# 10_Misc.net
KiCad netlist of a schematic drawn in Altium Designer
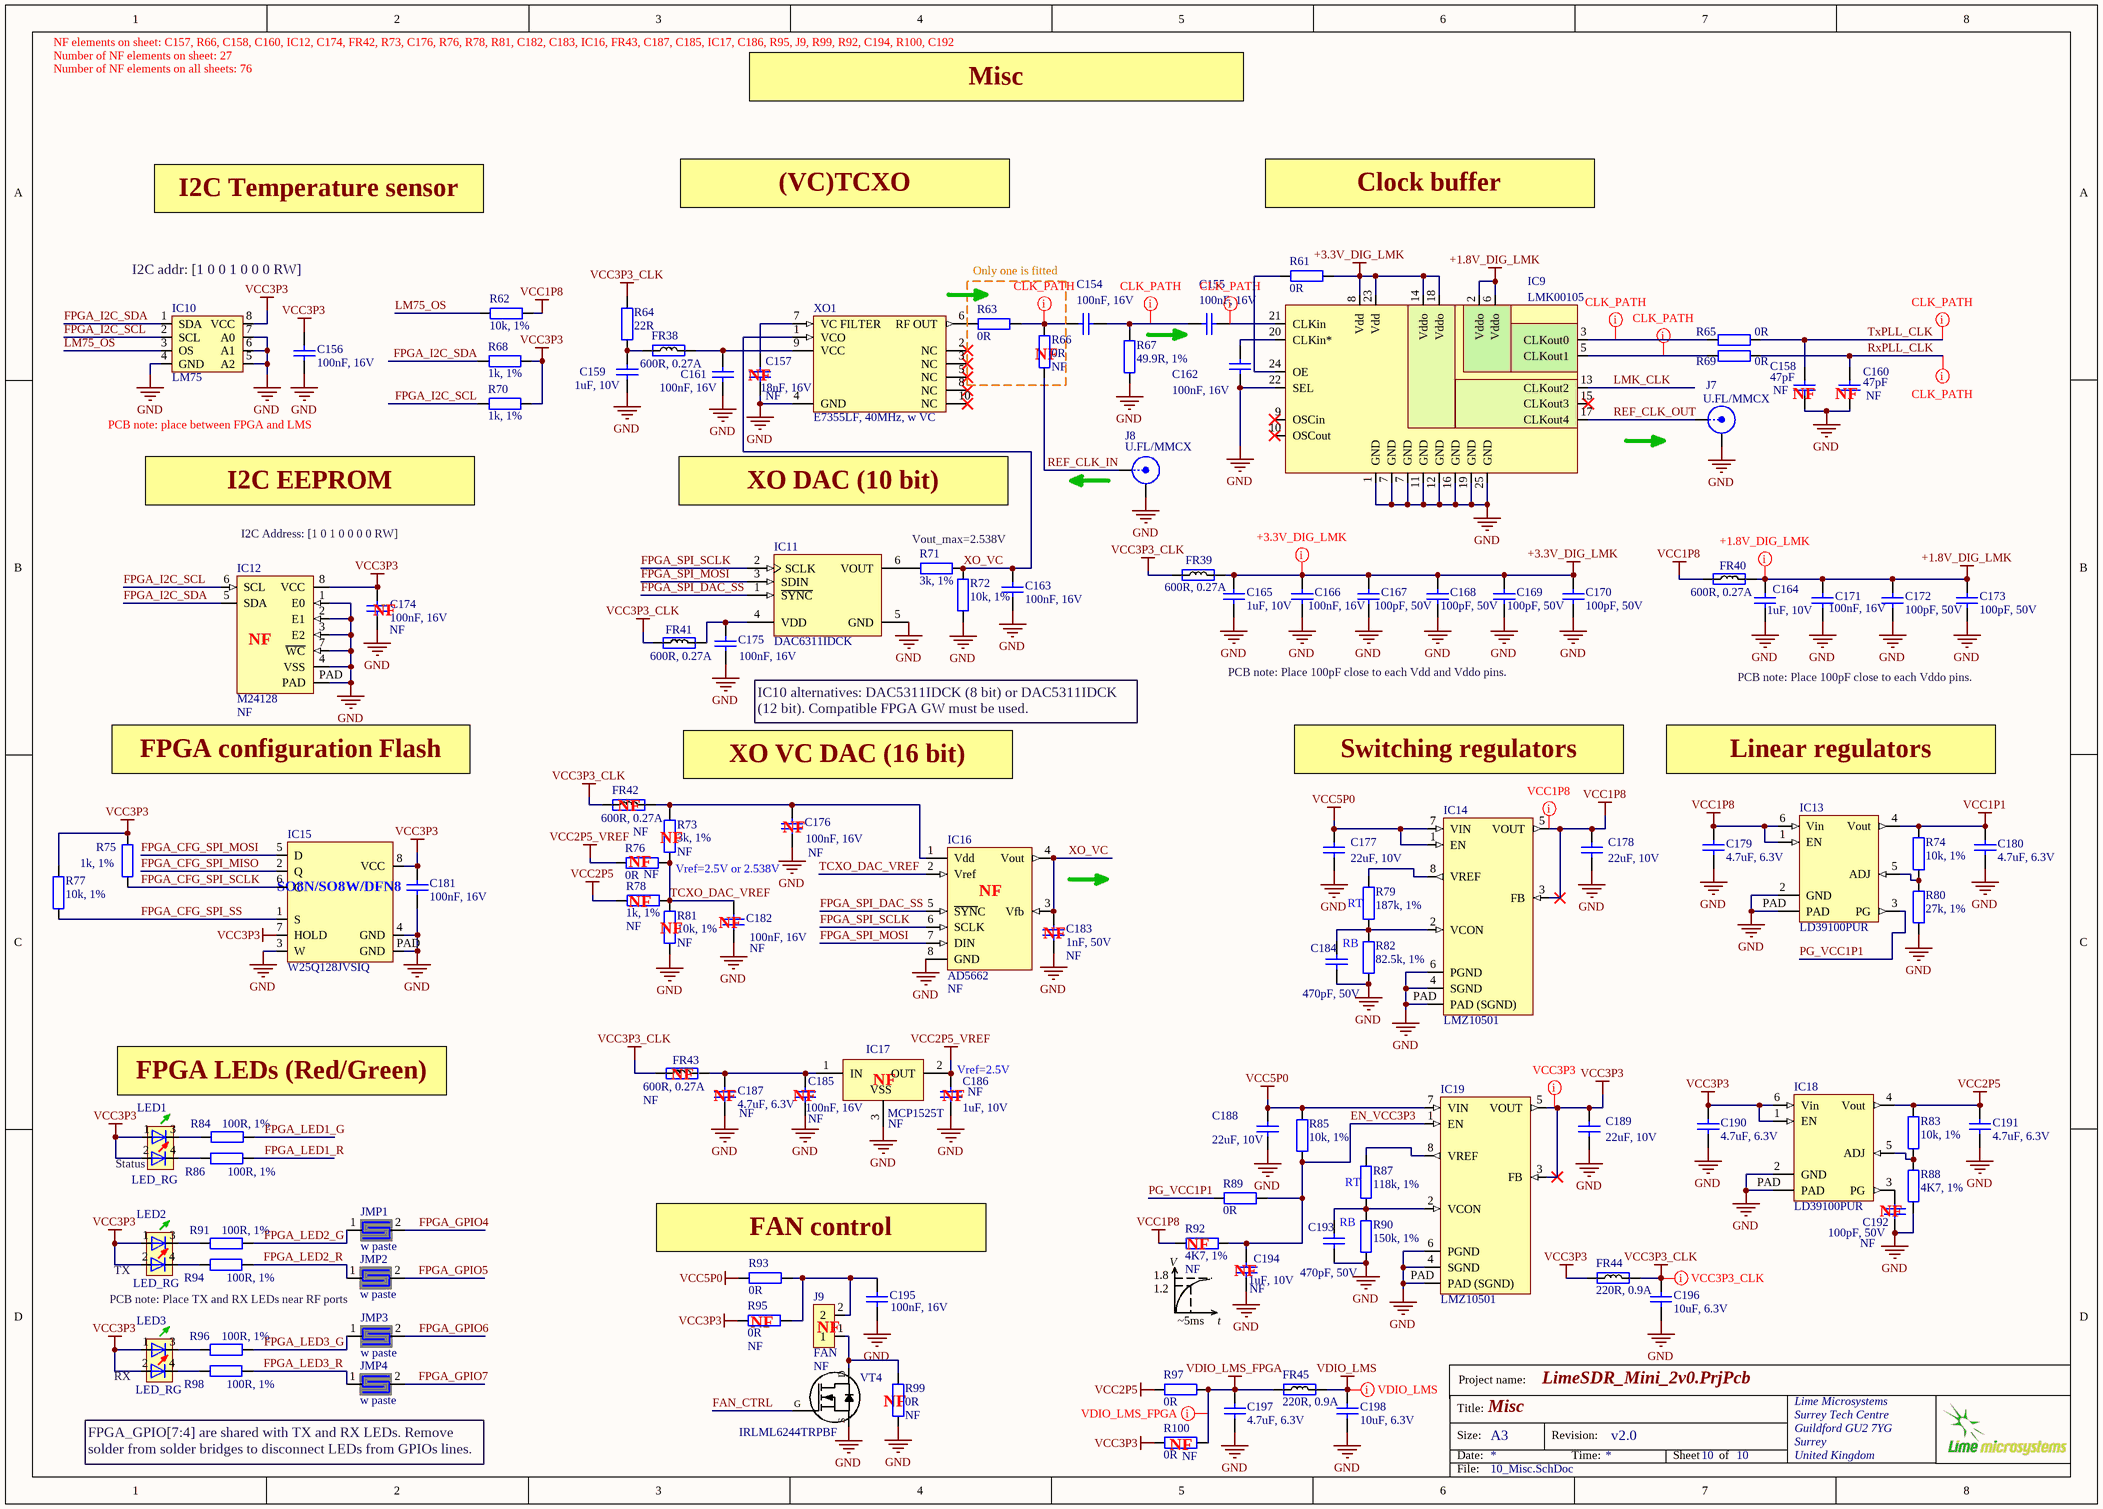
[diagram p0: 10_Misc.SchDoc]

(export (version "E")
  (design (tool "Eeschema 10.0.6"))
  (components
    (comp (ref "C154")
      (value "100nF, 16V")
      (footprint "CAP0402")
      (fields
        (field (name "MANUFACTURER") "Murata Electronics")
        (field (name "TOLERANCE") "10 %")
        (field (name "MANUFACTURER PART NUMBER") "GRM155R71C104KA88D")
      )
      (libsource (lib "LimeMicroAltiumLib_schLib") (part "Cap_0402"))
    )
    (comp (ref "C155")
      (value "100nF, 16V")
      (footprint "CAP0402")
      (fields
        (field (name "MANUFACTURER") "Murata Electronics")
        (field (name "TOLERANCE") "10 %")
        (field (name "MANUFACTURER PART NUMBER") "GRM155R71C104KA88D")
      )
      (libsource (lib "LimeMicroAltiumLib_schLib") (part "Cap_0402"))
    )
    (comp (ref "C156")
      (value "100nF, 16V")
      (footprint "CAP0402")
      (fields
        (field (name "TOLERANCE") "10 %")
        (field (name "MANUFACTURER") "Murata Electronics")
        (field (name "MANUFACTURER PART NUMBER") "GRM155R71C104KA88D")
      )
      (libsource (lib "") (part "Cap_0603_1"))
    )
    (comp (ref "C157")
      (value "18nF, 16V")
      (footprint "CAP0402")
      (fields
        (field (name "ASSEMBLY INFO") "NF")
        (field (name "MANUFACTURER") "Yageo")
        (field (name "TOLERANCE") "±10%")
      )
      (libsource (lib "LimeMicroAltiumLib_schLib") (part "Cap_0402"))
    )
    (comp (ref "C158")
      (value "47pF")
      (footprint "CAP0402")
      (fields
        (field (name "TOLERANCE") "±1%")
        (field (name "MANUFACTURER") "TDK Corporation")
        (field (name "ASSEMBLY INFO") "NF")
      )
      (libsource (lib "LimeMicroAltiumLib_schLib") (part "Cap_0402"))
    )
    (comp (ref "C159")
      (value "1uF, 10V")
      (footprint "CAP0402")
      (fields (field (name "MANUFACTURER") "TDK"))
      (libsource (lib "LimeMicroAltiumLib_schLib") (part "Cap_0402"))
    )
    (comp (ref "C160")
      (value "47pF")
      (footprint "CAP0402")
      (fields
        (field (name "TOLERANCE") "±1%")
        (field (name "MANUFACTURER") "TDK Corporation")
        (field (name "ASSEMBLY INFO") "NF")
      )
      (libsource (lib "LimeMicroAltiumLib_schLib") (part "Cap_0402"))
    )
    (comp (ref "C161")
      (value "100nF, 16V")
      (footprint "CAP0402")
      (fields
        (field (name "MANUFACTURER") "Murata Electronics")
        (field (name "TOLERANCE") "10 %")
        (field (name "MANUFACTURER PART NUMBER") "GRM155R71C104KA88D")
      )
      (libsource (lib "LimeMicroAltiumLib_schLib") (part "Cap_0402"))
    )
    (comp (ref "C162")
      (value "100nF, 16V")
      (footprint "CAP0402")
      (fields
        (field (name "MANUFACTURER") "Murata Electronics")
        (field (name "TOLERANCE") "10 %")
        (field (name "MANUFACTURER PART NUMBER") "GRM155R71C104KA88D")
      )
      (libsource (lib "LimeMicroAltiumLib_schLib") (part "Cap_0402"))
    )
    (comp (ref "C163")
      (value "100nF, 16V")
      (footprint "CAP0402")
      (fields
        (field (name "MANUFACTURER") "Murata Electronics")
        (field (name "TOLERANCE") "10 %")
        (field (name "MANUFACTURER PART NUMBER") "GRM155R71C104KA88D")
      )
      (libsource (lib "LimeMicroAltiumLib_schLib") (part "Cap_0402"))
    )
    (comp (ref "C164")
      (value "1uF, 10V")
      (footprint "CAP0402")
      (fields (field (name "MANUFACTURER") "TDK"))
      (libsource (lib "LimeMicroAltiumLib_schLib") (part "Cap_0402"))
    )
    (comp (ref "C165")
      (value "1uF, 10V")
      (footprint "CAP0402")
      (fields (field (name "MANUFACTURER") "TDK"))
      (libsource (lib "LimeMicroAltiumLib_schLib") (part "Cap_0402"))
    )
    (comp (ref "C166")
      (value "100nF, 16V")
      (footprint "CAP0402")
      (fields
        (field (name "MANUFACTURER") "Murata Electronics")
        (field (name "TOLERANCE") "10 %")
        (field (name "MANUFACTURER PART NUMBER") "GRM155R71C104KA88D")
      )
      (libsource (lib "LimeMicroAltiumLib_schLib") (part "Cap_0402"))
    )
    (comp (ref "C167")
      (value "100pF, 50V")
      (footprint "CAP0402")
      (fields (field (name "MANUFACTURER") "Yageo") (field (name "TOLERANCE") "±5%"))
      (libsource (lib "LimeMicroAltiumLib_schLib") (part "Cap_0402"))
    )
    (comp (ref "C168")
      (value "100pF, 50V")
      (footprint "CAP0402")
      (fields (field (name "MANUFACTURER") "Yageo") (field (name "TOLERANCE") "±5%"))
      (libsource (lib "LimeMicroAltiumLib_schLib") (part "Cap_0402"))
    )
    (comp (ref "C169")
      (value "100pF, 50V")
      (footprint "CAP0402")
      (fields (field (name "MANUFACTURER") "Yageo") (field (name "TOLERANCE") "±5%"))
      (libsource (lib "LimeMicroAltiumLib_schLib") (part "Cap_0402"))
    )
    (comp (ref "C170")
      (value "100pF, 50V")
      (footprint "CAP0402")
      (fields (field (name "MANUFACTURER") "Yageo") (field (name "TOLERANCE") "±5%"))
      (libsource (lib "LimeMicroAltiumLib_schLib") (part "Cap_0402"))
    )
    (comp (ref "C171")
      (value "100nF, 16V")
      (footprint "CAP0402")
      (fields
        (field (name "MANUFACTURER") "Murata Electronics")
        (field (name "TOLERANCE") "10 %")
        (field (name "MANUFACTURER PART NUMBER") "GRM155R71C104KA88D")
      )
      (libsource (lib "LimeMicroAltiumLib_schLib") (part "Cap_0402"))
    )
    (comp (ref "C172")
      (value "100pF, 50V")
      (footprint "CAP0402")
      (fields (field (name "MANUFACTURER") "Yageo") (field (name "TOLERANCE") "±5%"))
      (libsource (lib "LimeMicroAltiumLib_schLib") (part "Cap_0402"))
    )
    (comp (ref "C173")
      (value "100pF, 50V")
      (footprint "CAP0402")
      (fields (field (name "MANUFACTURER") "Yageo") (field (name "TOLERANCE") "±5%"))
      (libsource (lib "LimeMicroAltiumLib_schLib") (part "Cap_0402"))
    )
    (comp (ref "C174")
      (value "100nF, 16V")
      (footprint "CAP0402")
      (fields
        (field (name "TOLERANCE") "10 %")
        (field (name "MANUFACTURER") "Murata Electronics")
        (field (name "MANUFACTURER PART NUMBER") "GRM155R71C104KA88D")
        (field (name "ASSEMBLY INFO") "NF")
      )
      (libsource (lib "") (part "Cap_0603_1"))
    )
    (comp (ref "C175")
      (value "100nF, 16V")
      (footprint "CAP0402")
      (fields
        (field (name "TOLERANCE") "10 %")
        (field (name "MANUFACTURER") "Murata Electronics")
        (field (name "MANUFACTURER PART NUMBER") "GRM155R71C104KA88D")
      )
      (libsource (lib "") (part "Cap_0603_1"))
    )
    (comp (ref "C176")
      (value "100nF, 16V")
      (footprint "CAP0402")
      (fields
        (field (name "TOLERANCE") "10 %")
        (field (name "MANUFACTURER") "Murata Electronics")
        (field (name "MANUFACTURER PART NUMBER") "GRM155R71C104KA88D")
        (field (name "ASSEMBLY INFO") "NF")
      )
      (libsource (lib "") (part "Cap_0603_1"))
    )
    (comp (ref "C177")
      (value "22uF, 10V")
      (footprint "CAP0603")
      (fields (field (name "TOLERANCE") "20 %") (field (name "MANUFACTURER") "TDK Corporation"))
      (libsource (lib "") (part "Cap_0603_1"))
    )
    (comp (ref "C178")
      (value "22uF, 10V")
      (footprint "CAP0603")
      (fields (field (name "TOLERANCE") "20 %") (field (name "MANUFACTURER") "TDK Corporation"))
      (libsource (lib "") (part "Cap_0603_1"))
    )
    (comp (ref "C179")
      (value "4.7uF, 6.3V")
      (footprint "CAP0402")
      (fields
        (field (name "MANUFACTURER") "Murata Electronics North America")
        (field (name "TOLERANCE") "±20%")
      )
      (libsource (lib "LimeMicroAltiumLib_schLib") (part "Cap_0402"))
    )
    (comp (ref "C180")
      (value "4.7uF, 6.3V")
      (footprint "CAP0402")
      (fields
        (field (name "MANUFACTURER") "Murata Electronics North America")
        (field (name "TOLERANCE") "±20%")
      )
      (libsource (lib "LimeMicroAltiumLib_schLib") (part "Cap_0402"))
    )
    (comp (ref "C181")
      (value "100nF, 16V")
      (footprint "CAP0402")
      (fields
        (field (name "TOLERANCE") "10 %")
        (field (name "MANUFACTURER") "Murata Electronics")
        (field (name "MANUFACTURER PART NUMBER") "GRM155R71C104KA88D")
      )
      (libsource (lib "") (part "Cap_0603_1"))
    )
    (comp (ref "C182")
      (value "100nF, 16V")
      (footprint "LimeMicroAltiumLib_pcbLib_r03:CAP0402")
      (fields
        (field (name "TOLERANCE") "10 %")
        (field (name "MANUFACTURER") "Murata Electronics")
        (field (name "ASSEMBLY INFO") "NF")
      )
      (libsource (lib "LimeFPGAboard_schLib") (part "Cap_0603"))
    )
    (comp (ref "C183")
      (value "1nF, 50V")
      (footprint "LimeMicroAltiumLib_pcbLib_r03:CAP0402")
      (fields
        (field (name "ASSEMBLY INFO") "NF")
        (field (name "TOLERANCE") "10 %")
        (field (name "MANUFACTURER") "Murata Electronics")
      )
      (libsource (lib "") (part "Cap_0402_1"))
    )
    (comp (ref "C184")
      (value "470pF, 50V")
      (footprint "CAP0402")
      (fields (field (name "TOLERANCE") "±5%") (field (name "MANUFACTURER") "TDK Corporation"))
      (libsource (lib "LimeMicroAltiumLib_schLib") (part "Cap_0402"))
    )
    (comp (ref "C185")
      (value "100nF, 16V")
      (footprint "LimeMicroAltiumLib_pcbLib_r03:CAP0402")
      (fields
        (field (name "TOLERANCE") "10 %")
        (field (name "MANUFACTURER") "Murata Electronics")
        (field (name "ASSEMBLY INFO") "NF")
      )
      (libsource (lib "LimeFPGAboard_schLib") (part "Cap_0603"))
    )
    (comp (ref "C186")
      (value "1uF, 10V")
      (footprint "CAP0402")
      (fields (field (name "ASSEMBLY INFO") "NF") (field (name "MANUFACTURER") "TDK"))
      (libsource (lib "LimeMicroAltiumLib_schLib") (part "Cap_0402"))
    )
    (comp (ref "C187")
      (value "4.7uF, 6.3V")
      (footprint "CAP0402")
      (fields
        (field (name "ASSEMBLY INFO") "NF")
        (field (name "MANUFACTURER") "Murata Electronics North America")
        (field (name "TOLERANCE") "±20%")
      )
      (libsource (lib "LimeMicroAltiumLib_schLib") (part "Cap_0402"))
    )
    (comp (ref "C188")
      (value "22uF, 10V")
      (footprint "CAP0603")
      (fields (field (name "TOLERANCE") "20 %") (field (name "MANUFACTURER") "TDK Corporation"))
      (libsource (lib "") (part "Cap_0603_1"))
    )
    (comp (ref "C189")
      (value "22uF, 10V")
      (footprint "CAP0603")
      (fields (field (name "TOLERANCE") "20 %") (field (name "MANUFACTURER") "TDK Corporation"))
      (libsource (lib "") (part "Cap_0603_1"))
    )
    (comp (ref "C190")
      (value "4.7uF, 6.3V")
      (footprint "CAP0402")
      (fields
        (field (name "MANUFACTURER") "Murata Electronics North America")
        (field (name "TOLERANCE") "±20%")
      )
      (libsource (lib "LimeMicroAltiumLib_schLib") (part "Cap_0402"))
    )
    (comp (ref "C191")
      (value "4.7uF, 6.3V")
      (footprint "CAP0402")
      (fields
        (field (name "MANUFACTURER") "Murata Electronics North America")
        (field (name "TOLERANCE") "±20%")
      )
      (libsource (lib "LimeMicroAltiumLib_schLib") (part "Cap_0402"))
    )
    (comp (ref "C192")
      (value "100pF, 50V")
      (footprint "CAP0402")
      (fields
        (field (name "ASSEMBLY INFO") "NF")
        (field (name "MANUFACTURER") "Yageo")
        (field (name "TOLERANCE") "±5%")
      )
      (libsource (lib "LimeMicroAltiumLib_schLib") (part "Cap_0402"))
    )
    (comp (ref "C193")
      (value "470pF, 50V")
      (footprint "CAP0402")
      (fields (field (name "TOLERANCE") "±5%") (field (name "MANUFACTURER") "TDK Corporation"))
      (libsource (lib "LimeMicroAltiumLib_schLib") (part "Cap_0402"))
    )
    (comp (ref "C194")
      (value "1uF, 10V")
      (footprint "CAP0402")
      (fields (field (name "ASSEMBLY INFO") "NF") (field (name "MANUFACTURER") "TDK"))
      (libsource (lib "LimeMicroAltiumLib_schLib") (part "Cap_0402"))
    )
    (comp (ref "C195")
      (value "100nF, 16V")
      (footprint "CAP0402")
      (fields
        (field (name "TOLERANCE") "10 %")
        (field (name "MANUFACTURER") "Murata Electronics")
        (field (name "MANUFACTURER PART NUMBER") "GRM155R71C104KA88D")
      )
      (libsource (lib "") (part "Cap_0603_1"))
    )
    (comp (ref "C196")
      (value "10uF, 6.3V")
      (footprint "CAP0603")
      (fields (field (name "TOLERANCE") "±20%") (field (name "MANUFACTURER") "Yageo"))
      (libsource (lib "") (part "Cap_0603_1"))
    )
    (comp (ref "C197")
      (value "4.7uF, 6.3V")
      (footprint "CAP0402")
      (fields
        (field (name "MANUFACTURER") "Murata Electronics North America")
        (field (name "TOLERANCE") "±20%")
      )
      (libsource (lib "LimeMicroAltiumLib_schLib") (part "Cap_0402"))
    )
    (comp (ref "C198")
      (value "10uF, 6.3V")
      (footprint "CAP0603")
      (fields (field (name "TOLERANCE") "±20%") (field (name "MANUFACTURER") "Yageo"))
      (libsource (lib "") (part "Cap_0603_1"))
    )
    (comp (ref "FR38")
      (value "600R, 0.27A")
      (footprint "RES0201")
      (fields (field (name "MANUFACTURER") "Taiyo Yuden"))
      (libsource (lib "LimeMicroAltiumLib_schLib") (part "Ferrite"))
    )
    (comp (ref "FR39")
      (value "600R, 0.27A")
      (footprint "RES0201")
      (fields (field (name "MANUFACTURER") "Taiyo Yuden"))
      (libsource (lib "LimeMicroAltiumLib_schLib") (part "Ferrite"))
    )
    (comp (ref "FR40")
      (value "600R, 0.27A")
      (footprint "RES0201")
      (fields (field (name "MANUFACTURER") "Taiyo Yuden"))
      (libsource (lib "LimeMicroAltiumLib_schLib") (part "Ferrite"))
    )
    (comp (ref "FR41")
      (value "600R, 0.27A")
      (footprint "RES0201")
      (fields (field (name "MANUFACTURER") "Taiyo Yuden"))
      (libsource (lib "LimeMicroAltiumLib_schLib") (part "Ferrite"))
    )
    (comp (ref "FR42")
      (value "600R, 0.27A")
      (footprint "RES0201")
      (fields (field (name "MANUFACTURER") "Taiyo Yuden") (field (name "ASSEMBLY INFO") "NF"))
      (libsource (lib "LimeMicroAltiumLib_schLib") (part "Ferrite"))
    )
    (comp (ref "FR43")
      (value "600R, 0.27A")
      (footprint "RES0201")
      (fields (field (name "MANUFACTURER") "Taiyo Yuden") (field (name "ASSEMBLY INFO") "NF"))
      (libsource (lib "LimeMicroAltiumLib_schLib") (part "Ferrite"))
    )
    (comp (ref "FR44")
      (value "220R, 0.9A")
      (footprint "RES0402")
      (fields (field (name "MANUFACTURER") "TDK Corporation"))
      (libsource (lib "LimeFPGAboard_schLib") (part "Ferrite"))
    )
    (comp (ref "FR45")
      (value "220R, 0.9A")
      (footprint "RES0402")
      (fields (field (name "MANUFACTURER") "TDK Corporation"))
      (libsource (lib "LimeFPGAboard_schLib") (part "Ferrite"))
    )
    (comp (ref "IC9")
      (value "LMK00105")
      (footprint "LMK00105SQ")
      (fields (field (name "MANUFACTURER") "Texas Instruments"))
      (libsource (lib "LimeMicroAltiumLib_schLib") (part "LMK00105"))
    )
    (comp (ref "IC10")
      (value "LM75")
      (footprint "HWSON8_LM75")
      (fields (field (name "MANUFACTURER") "NXP Semiconductors"))
      (libsource (lib "LimeMicroAltiumLib_schLib") (part "LM75"))
    )
    (comp (ref "IC11")
      (value "DAC6311IDCK")
      (footprint "AD5601_SOT23-6")
      (fields (field (name "MANUFACTURER") "Texas Instruments"))
      (libsource (lib "LimeMicroAltiumLib_schLib") (part "AD5601BKSZ-REEL7"))
    )
    (comp (ref "IC12")
      (value "M24128")
      (footprint "M24128-DFMC6TG")
      (fields (field (name "MANUFACTURER") "STMicroelectronics") (field (name "ASSEMBLY INFO") "NF"))
      (libsource (lib "LimeMicroAltiumLib_schLib") (part "M24128-DFMC6TG"))
    )
    (comp (ref "IC13")
      (value "LD39100PUR")
      (footprint "LD39100PUR")
      (fields (field (name "MANUFACTURER") "STMicroelectronics"))
      (libsource (lib "LimeMicroAltiumLib_schLib") (part "LD39100PUR"))
    )
    (comp (ref "IC14")
      (value "LMZ10501")
      (footprint "LMZ10501")
      (fields (field (name "MANUFACTURER") "Texas Instruments"))
      (libsource (lib "LimeMicroAltiumLib_schLib") (part "LMZ10501"))
    )
    (comp (ref "IC15")
      (value "W25Q128JVSIQ")
      (footprint "S25FL164K_WSON8_DFN6")
      (fields (field (name "MANUFACTURER") "Winbond"))
      (libsource (lib "LimeMicroAltiumLib_schLib_r03") (part "M25P40_with_pad"))
    )
    (comp (ref "IC16")
      (value "AD5662")
      (footprint "LimeMicroAltiumLib_pcbLib_r03:AD5662_SOT23-8")
      (fields (field (name "MANUFACTURER") "Analog Devices Inc.") (field (name "ASSEMBLY INFO") "NF"))
      (libsource (lib "LimeMicroAltiumLib_schLib") (part "AD5662"))
    )
    (comp (ref "IC17")
      (value "MCP1525T")
      (footprint "LimeMicroAltiumLib_pcbLib_r03:SOT23-3_v2")
      (description "2.5V Voltage Reference, 3-Pin SOT-23, Industrial Temperature, Tape and Reel")
      (fields
        (field (name "MANUFACTURER") "Microchip Technology")
        (field (name "TOLERANCE") "±1%")
        (field (name "ASSEMBLY INFO") "NF")
      )
      (libsource (lib "LimeMicroAltiumLib_schLib") (part "MCP1525T-I/TT"))
    )
    (comp (ref "IC18")
      (value "LD39100PUR")
      (footprint "LD39100PUR")
      (fields (field (name "MANUFACTURER") "STMicroelectronics"))
      (libsource (lib "LimeMicroAltiumLib_schLib") (part "LD39100PUR"))
    )
    (comp (ref "IC19")
      (value "LMZ10501")
      (footprint "LMZ10501")
      (fields (field (name "MANUFACTURER") "Texas Instruments"))
      (libsource (lib "LimeMicroAltiumLib_schLib") (part "LMZ10501"))
    )
    (comp (ref "J7")
      (value "U.FL/MMCX")
      (footprint "MMCX_UFL_conn_u")
      (description "CONN UMC RCPT STR 50 OHM SMD")
      (fields (field (name "MANUFACTURER") "Molex, LLC"))
      (libsource (lib "LimeMicroAltiumLib_schLib") (part "RF_IF_connector"))
    )
    (comp (ref "J8")
      (value "U.FL/MMCX")
      (footprint "MMCX_UFL_conn_u")
      (description "CONN UMC RCPT STR 50 OHM SMD")
      (fields (field (name "MANUFACTURER") "Molex, LLC"))
      (libsource (lib "LimeMicroAltiumLib_schLib") (part "RF_IF_connector"))
    )
    (comp (ref "J9")
      (value "FAN")
      (footprint "Header2x1_TH_v2")
      (fields (field (name "ASSEMBLY INFO") "NF") (field (name "MANUFACTURER") "3M"))
      (libsource (lib "LimeFPGAboard_schLib") (part "Jumper"))
    )
    (comp (ref "JMP1")
      (value "w paste")
      (footprint "JUMPER_0P15_W_PASTE")
      (libsource (lib "LimeMicroAltiumLib_schLib_r03") (part "JUMPER_W_PASTE"))
    )
    (comp (ref "JMP2")
      (value "w paste")
      (footprint "JUMPER_0P15_W_PASTE")
      (libsource (lib "LimeMicroAltiumLib_schLib_r03") (part "JUMPER_W_PASTE"))
    )
    (comp (ref "JMP3")
      (value "w paste")
      (footprint "JUMPER_0P15_W_PASTE")
      (libsource (lib "LimeMicroAltiumLib_schLib_r03") (part "JUMPER_W_PASTE"))
    )
    (comp (ref "JMP4")
      (value "w paste")
      (footprint "JUMPER_0P15_W_PASTE")
      (libsource (lib "LimeMicroAltiumLib_schLib_r03") (part "JUMPER_W_PASTE"))
    )
    (comp (ref "LED1")
      (value "LED_RG")
      (footprint "LED-2x0603")
      (fields (field (name "MANUFACTURER") "Avago Technologies US Inc."))
      (libsource (lib "LimeMicroAltiumLib_schLib") (part "LED_green_red_SMD"))
    )
    (comp (ref "LED2")
      (value "LED_RG")
      (footprint "LED-2x0603")
      (fields (field (name "MANUFACTURER") "Avago Technologies US Inc."))
      (libsource (lib "LimeMicroAltiumLib_schLib") (part "LED_green_red_SMD"))
    )
    (comp (ref "LED3")
      (value "LED_RG")
      (footprint "LED-2x0603")
      (fields (field (name "MANUFACTURER") "Avago Technologies US Inc."))
      (libsource (lib "LimeMicroAltiumLib_schLib") (part "LED_green_red_SMD"))
    )
    (comp (ref "R61")
      (value "0R")
      (footprint "RES0402")
      (fields (field (name "MANUFACTURER") "Yageo") (field (name "TOLERANCE") "Jumper"))
      (libsource (lib "LimeMicroAltiumLib_schLib") (part "Res_0402"))
    )
    (comp (ref "R62")
      (value "10k, 1%")
      (footprint "RES0402")
      (fields (field (name "MANUFACTURER") "Yageo") (field (name "TOLERANCE") "±1%"))
      (libsource (lib "LimeMicroAltiumLib_schLib") (part "Res_0402"))
    )
    (comp (ref "R63")
      (value "0R")
      (footprint "RES0402")
      (fields (field (name "MANUFACTURER") "Yageo") (field (name "TOLERANCE") "Jumper"))
      (libsource (lib "LimeMicroAltiumLib_schLib") (part "Res_0402"))
    )
    (comp (ref "R64")
      (value "22R")
      (footprint "RES0402")
      (fields (field (name "TOLERANCE") "±1%") (field (name "MANUFACTURER") "Yageo"))
      (libsource (lib "LimeFPGAboard_schLib") (part "Res_0402"))
    )
    (comp (ref "R65")
      (value "0R")
      (footprint "RES0402")
      (fields (field (name "MANUFACTURER") "Yageo") (field (name "TOLERANCE") "Jumper"))
      (libsource (lib "LimeFPGAboard_schLib") (part "Res_0402"))
    )
    (comp (ref "R66")
      (value "0R")
      (footprint "RES0402")
      (fields
        (field (name "ASSEMBLY INFO") "NF")
        (field (name "MANUFACTURER") "Yageo")
        (field (name "TOLERANCE") "Jumper")
      )
      (libsource (lib "LimeMicroAltiumLib_schLib") (part "Res_0402"))
    )
    (comp (ref "R67")
      (value "49.9R, 1%")
      (footprint "RES0402")
      (fields
        (field (name "TOLERANCE") "±1%")
        (field (name "MANUFACTURER") "Samsung Electro-Mechanics America, Inc.")
      )
      (libsource (lib "LimeMicroAltiumLib_schLib") (part "Res_0402"))
    )
    (comp (ref "R68")
      (value "1k, 1%")
      (footprint "RES0402")
      (fields (field (name "MANUFACTURER") "Stackpole Electronics Inc") (field (name "TOLERANCE") "±1%"))
      (libsource (lib "LimeMicroAltiumLib_schLib") (part "Res_0402"))
    )
    (comp (ref "R69")
      (value "0R")
      (footprint "RES0402")
      (fields (field (name "MANUFACTURER") "Yageo") (field (name "TOLERANCE") "Jumper"))
      (libsource (lib "LimeFPGAboard_schLib") (part "Res_0402"))
    )
    (comp (ref "R70")
      (value "1k, 1%")
      (footprint "RES0402")
      (fields (field (name "MANUFACTURER") "Stackpole Electronics Inc") (field (name "TOLERANCE") "±1%"))
      (libsource (lib "LimeMicroAltiumLib_schLib") (part "Res_0402"))
    )
    (comp (ref "R71")
      (value "3k, 1%")
      (footprint "RES0402")
      (fields (field (name "TOLERANCE") "±1%") (field (name "MANUFACTURER") "Vishay Dale"))
      (libsource (lib "LimeMicroAltiumLib_schLib") (part "Res_0402"))
    )
    (comp (ref "R72")
      (value "10k, 1%")
      (footprint "RES0402")
      (fields (field (name "MANUFACTURER") "Yageo") (field (name "TOLERANCE") "±1%"))
      (libsource (lib "LimeMicroAltiumLib_schLib") (part "Res_0402"))
    )
    (comp (ref "R73")
      (value "3k, 1%")
      (footprint "LimeMicroAltiumLib_pcbLib_r03:RES0402")
      (fields
        (field (name "ASSEMBLY INFO") "NF")
        (field (name "TOLERANCE") "±1%")
        (field (name "MANUFACTURER") "Vishay Dale")
      )
      (libsource (lib "") (part "Res_0402_1"))
    )
    (comp (ref "R74")
      (value "10k, 1%")
      (footprint "RES0402")
      (fields (field (name "MANUFACTURER") "Yageo") (field (name "TOLERANCE") "±1%"))
      (libsource (lib "LimeMicroAltiumLib_schLib") (part "Res_0402"))
    )
    (comp (ref "R75")
      (value "1k, 1%")
      (footprint "RES0402")
      (fields (field (name "MANUFACTURER") "Stackpole Electronics Inc") (field (name "TOLERANCE") "±1%"))
      (libsource (lib "LimeMicroAltiumLib_schLib") (part "Res_0402"))
    )
    (comp (ref "R76")
      (value "0R")
      (footprint "RES0402")
      (fields
        (field (name "ASSEMBLY INFO") "NF")
        (field (name "MANUFACTURER") "Yageo")
        (field (name "TOLERANCE") "Jumper")
      )
      (libsource (lib "LimeMicroAltiumLib_schLib") (part "Res_0402"))
    )
    (comp (ref "R77")
      (value "10k, 1%")
      (footprint "RES0402")
      (fields (field (name "MANUFACTURER") "Yageo") (field (name "TOLERANCE") "±1%"))
      (libsource (lib "LimeMicroAltiumLib_schLib") (part "Res_0402"))
    )
    (comp (ref "R78")
      (value "1k, 1%")
      (footprint "RES0402")
      (fields
        (field (name "ASSEMBLY INFO") "NF")
        (field (name "MANUFACTURER") "Stackpole Electronics Inc")
        (field (name "TOLERANCE") "±1%")
      )
      (libsource (lib "") (part "Res_0402_1"))
    )
    (comp (ref "R79")
      (value "187k, 1%")
      (footprint "RES0402")
      (fields (field (name "TOLERANCE") "±1%") (field (name "MANUFACTURER") "Yageo"))
      (libsource (lib "LimeMicroAltiumLib_schLib") (part "Res_0402"))
    )
    (comp (ref "R80")
      (value "27k, 1%")
      (footprint "RES0402")
      (fields (field (name "MANUFACTURER") "Yageo") (field (name "TOLERANCE") "1%"))
      (libsource (lib "LimeFPGAboard_schLib") (part "Res_0402"))
    )
    (comp (ref "R81")
      (value "10k, 1%")
      (footprint "LimeMicroAltiumLib_pcbLib_r03:RES0402")
      (fields
        (field (name "ASSEMBLY INFO") "NF")
        (field (name "MANUFACTURER") "Yageo")
        (field (name "TOLERANCE") "±1%")
      )
      (libsource (lib "") (part "Res_0402_1"))
    )
    (comp (ref "R82")
      (value "82.5k, 1%")
      (footprint "RES0402")
      (fields (field (name "TOLERANCE") "±1%") (field (name "MANUFACTURER") "Yageo"))
      (libsource (lib "LimeMicroAltiumLib_schLib") (part "Res_0402"))
    )
    (comp (ref "R83")
      (value "10k, 1%")
      (footprint "RES0402")
      (fields (field (name "MANUFACTURER") "Yageo") (field (name "TOLERANCE") "±1%"))
      (libsource (lib "LimeMicroAltiumLib_schLib") (part "Res_0402"))
    )
    (comp (ref "R84")
      (value "100R, 1%")
      (footprint "RES0402")
      (fields (field (name "TOLERANCE") "±1%") (field (name "MANUFACTURER") "Stackpole Electronics Inc."))
      (libsource (lib "LimeMicroAltiumLib_schLib") (part "Res_0402"))
    )
    (comp (ref "R85")
      (value "10k, 1%")
      (footprint "RES0402")
      (fields (field (name "MANUFACTURER") "Yageo") (field (name "TOLERANCE") "±1%"))
      (libsource (lib "LimeMicroAltiumLib_schLib") (part "Res_0402"))
    )
    (comp (ref "R86")
      (value "100R, 1%")
      (footprint "RES0402")
      (fields (field (name "TOLERANCE") "±1%") (field (name "MANUFACTURER") "Stackpole Electronics Inc."))
      (libsource (lib "LimeMicroAltiumLib_schLib") (part "Res_0402"))
    )
    (comp (ref "R87")
      (value "118k, 1%")
      (footprint "RES0402")
      (fields (field (name "MANUFACTURER") "Yageo") (field (name "TOLERANCE") "±1%"))
      (libsource (lib "LimeMicroAltiumLib_schLib") (part "Res_0402"))
    )
    (comp (ref "R88")
      (value "4K7, 1%")
      (footprint "RES0402")
      (fields (field (name "MANUFACTURER") "Yageo") (field (name "TOLERANCE") "±1%"))
      (libsource (lib "LimeFPGAboard_schLib") (part "Res_0402"))
    )
    (comp (ref "R89")
      (value "0R")
      (footprint "RES0402")
      (fields (field (name "MANUFACTURER") "Yageo") (field (name "TOLERANCE") "Jumper"))
      (libsource (lib "LimeMicroAltiumLib_schLib") (part "Res_0402"))
    )
    (comp (ref "R90")
      (value "150k, 1%")
      (footprint "RES0402")
      (fields (field (name "TOLERANCE") "±5%") (field (name "MANUFACTURER") "Yageo"))
      (libsource (lib "LimeMicroAltiumLib_schLib") (part "Res_0402"))
    )
    (comp (ref "R91")
      (value "100R, 1%")
      (footprint "RES0402")
      (fields (field (name "TOLERANCE") "±1%") (field (name "MANUFACTURER") "Stackpole Electronics Inc."))
      (libsource (lib "LimeMicroAltiumLib_schLib") (part "Res_0402"))
    )
    (comp (ref "R92")
      (value "4K7, 1%")
      (footprint "RES0402")
      (fields
        (field (name "MANUFACTURER") "Yageo")
        (field (name "TOLERANCE") "±1%")
        (field (name "ASSEMBLY INFO") "NF")
      )
      (libsource (lib "LimeFPGAboard_schLib") (part "Res_0402"))
    )
    (comp (ref "R93")
      (value "0R")
      (footprint "RES0402")
      (fields (field (name "MANUFACTURER") "Yageo") (field (name "TOLERANCE") "Jumper"))
      (libsource (lib "LimeMicroAltiumLib_schLib") (part "Res_0402"))
    )
    (comp (ref "R94")
      (value "100R, 1%")
      (footprint "RES0402")
      (fields (field (name "TOLERANCE") "±1%") (field (name "MANUFACTURER") "Stackpole Electronics Inc."))
      (libsource (lib "LimeMicroAltiumLib_schLib") (part "Res_0402"))
    )
    (comp (ref "R95")
      (value "0R")
      (footprint "RES0402")
      (fields
        (field (name "ASSEMBLY INFO") "NF")
        (field (name "MANUFACTURER") "Yageo")
        (field (name "TOLERANCE") "Jumper")
      )
      (libsource (lib "LimeMicroAltiumLib_schLib") (part "Res_0402"))
    )
    (comp (ref "R96")
      (value "100R, 1%")
      (footprint "RES0402")
      (fields (field (name "TOLERANCE") "±1%") (field (name "MANUFACTURER") "Stackpole Electronics Inc."))
      (libsource (lib "LimeMicroAltiumLib_schLib") (part "Res_0402"))
    )
    (comp (ref "R97")
      (value "0R")
      (footprint "RES0402")
      (fields (field (name "MANUFACTURER") "Yageo") (field (name "TOLERANCE") "Jumper"))
      (libsource (lib "LimeFPGAboard_schLib") (part "Res_0402"))
    )
    (comp (ref "R98")
      (value "100R, 1%")
      (footprint "RES0402")
      (fields (field (name "TOLERANCE") "±1%") (field (name "MANUFACTURER") "Stackpole Electronics Inc."))
      (libsource (lib "LimeMicroAltiumLib_schLib") (part "Res_0402"))
    )
    (comp (ref "R99")
      (value "0R")
      (footprint "RES0402")
      (fields
        (field (name "ASSEMBLY INFO") "NF")
        (field (name "MANUFACTURER") "Yageo")
        (field (name "TOLERANCE") "Jumper")
      )
      (libsource (lib "LimeMicroAltiumLib_schLib") (part "Res_0402"))
    )
    (comp (ref "R100")
      (value "0R")
      (footprint "RES0402")
      (fields
        (field (name "MANUFACTURER") "Yageo")
        (field (name "ASSEMBLY INFO") "NF")
        (field (name "TOLERANCE") "Jumper")
      )
      (libsource (lib "LimeFPGAboard_schLib") (part "Res_0402"))
    )
    (comp (ref "VT4")
      (value "IRLML6244TRPBF")
      (footprint "SOT23-3")
      (description "NDS331N")
      (fields (field (name "MANUFACTURER") "Infineon Technologies"))
      (libsource (lib "LimeFPGAboard_schLib") (part "NDS331N"))
    )
    (comp (ref "XO1")
      (value "E7355LF, 40MHz, w VC")
      (footprint "RAKON_RTX5032A")
      (fields (field (name "MANUFACTURER") "Rakon"))
      (libsource (lib "LimeMicroAltiumLib_schLib") (part "Rakon_RTX5032A"))
    )
  )
  (nets
    (net (code "1") (name "+1.8V_DIG_LMK") (class "Default")
      (node (ref "C164") (pin "2") (pinfunction "2_2") (pintype "passive"))
      (node (ref "C171") (pin "2") (pinfunction "2_2") (pintype "passive"))
      (node (ref "C172") (pin "2") (pinfunction "2_2") (pintype "passive"))
      (node (ref "C173") (pin "2") (pinfunction "2_2") (pintype "passive"))
      (node (ref "FR40") (pin "2") (pinfunction "2_2") (pintype "passive"))
      (node (ref "IC9") (pin "2") (pinfunction "Vddo_2") (pintype "passive"))
      (node (ref "IC9") (pin "6") (pinfunction "Vddo_6") (pintype "passive"))
    )
    (net (code "2") (name "+3.3V_DIG_LMK") (class "Default")
      (node (ref "C165") (pin "2") (pinfunction "2_2") (pintype "passive"))
      (node (ref "C166") (pin "2") (pinfunction "2_2") (pintype "passive"))
      (node (ref "C167") (pin "2") (pinfunction "2_2") (pintype "passive"))
      (node (ref "C168") (pin "2") (pinfunction "2_2") (pintype "passive"))
      (node (ref "C169") (pin "2") (pinfunction "2_2") (pintype "passive"))
      (node (ref "C170") (pin "2") (pinfunction "2_2") (pintype "passive"))
      (node (ref "FR39") (pin "2") (pinfunction "2_2") (pintype "passive"))
      (node (ref "IC9") (pin "14") (pinfunction "Vddo_14") (pintype "passive"))
      (node (ref "IC9") (pin "18") (pinfunction "Vddo_18") (pintype "passive"))
      (node (ref "IC9") (pin "23") (pinfunction "Vdd_23") (pintype "passive"))
      (node (ref "IC9") (pin "8") (pinfunction "Vdd_8") (pintype "passive"))
      (node (ref "R61") (pin "2") (pinfunction "2_2") (pintype "passive"))
    )
    (net (code "3") (name "/EN_VCC3P3") (class "Default")
      (node (ref "C194") (pin "2") (pinfunction "2_2") (pintype "passive"))
      (node (ref "IC19") (pin "1") (pinfunction "EN_1") (pintype "input"))
      (node (ref "R85") (pin "1") (pinfunction "1_1") (pintype "passive"))
      (node (ref "R89") (pin "2") (pinfunction "2_2") (pintype "passive"))
      (node (ref "R92") (pin "1") (pinfunction "1_1") (pintype "passive"))
    )
    (net (code "4") (name "/FAN_CTRL") (class "Default")
      (node (ref "VT4") (pin "G") (pinfunction "G_G") (pintype "passive"))
    )
    (net (code "5") (name "/FPGA_CFG_SPI_MISO") (class "Default")
      (node (ref "IC15") (pin "2") (pinfunction "Q_2") (pintype "passive"))
    )
    (net (code "6") (name "/FPGA_CFG_SPI_MOSI") (class "Default")
      (node (ref "IC15") (pin "5") (pinfunction "D_5") (pintype "passive"))
    )
    (net (code "7") (name "/FPGA_CFG_SPI_SCLK") (class "Default")
      (node (ref "IC15") (pin "6") (pinfunction "C_6") (pintype "passive"))
      (node (ref "R75") (pin "1") (pinfunction "1_1") (pintype "passive"))
    )
    (net (code "8") (name "/FPGA_CFG_SPI_SS") (class "Default")
      (node (ref "IC15") (pin "1") (pinfunction "S_1") (pintype "passive"))
      (node (ref "R77") (pin "1") (pinfunction "1_1") (pintype "passive"))
    )
    (net (code "9") (name "/FPGA_GPIO4") (class "Default")
      (node (ref "JMP1") (pin "2") (pinfunction "2_2") (pintype "passive"))
    )
    (net (code "10") (name "/FPGA_GPIO5") (class "Default")
      (node (ref "JMP2") (pin "2") (pinfunction "2_2") (pintype "passive"))
    )
    (net (code "11") (name "/FPGA_GPIO6") (class "Default")
      (node (ref "JMP3") (pin "2") (pinfunction "2_2") (pintype "passive"))
    )
    (net (code "12") (name "/FPGA_GPIO7") (class "Default")
      (node (ref "JMP4") (pin "2") (pinfunction "2_2") (pintype "passive"))
    )
    (net (code "13") (name "/FPGA_I2C_SCL") (class "Default")
      (node (ref "IC10") (pin "2") (pinfunction "SCL_2") (pintype "passive"))
      (node (ref "IC12") (pin "6") (pinfunction "SCL_6") (pintype "input"))
      (node (ref "R70") (pin "2") (pinfunction "2_2") (pintype "passive"))
    )
    (net (code "14") (name "/FPGA_I2C_SDA") (class "Default")
      (node (ref "IC10") (pin "1") (pinfunction "SDA_1") (pintype "passive"))
      (node (ref "IC12") (pin "5") (pinfunction "SDA_5") (pintype "bidirectional"))
      (node (ref "R68") (pin "2") (pinfunction "2_2") (pintype "passive"))
    )
    (net (code "15") (name "/FPGA_LED1_G") (class "Default")
      (node (ref "R84") (pin "2") (pinfunction "2_2") (pintype "passive"))
    )
    (net (code "16") (name "/FPGA_LED1_R") (class "Default")
      (node (ref "R86") (pin "2") (pinfunction "2_2") (pintype "passive"))
    )
    (net (code "17") (name "/FPGA_LED2_G") (class "Default")
      (node (ref "JMP1") (pin "1") (pinfunction "1_1") (pintype "passive"))
      (node (ref "R91") (pin "2") (pinfunction "2_2") (pintype "passive"))
    )
    (net (code "18") (name "/FPGA_LED2_R") (class "Default")
      (node (ref "JMP2") (pin "1") (pinfunction "1_1") (pintype "passive"))
      (node (ref "R94") (pin "2") (pinfunction "2_2") (pintype "passive"))
    )
    (net (code "19") (name "/FPGA_LED3_G") (class "Default")
      (node (ref "JMP3") (pin "1") (pinfunction "1_1") (pintype "passive"))
      (node (ref "R96") (pin "2") (pinfunction "2_2") (pintype "passive"))
    )
    (net (code "20") (name "/FPGA_LED3_R") (class "Default")
      (node (ref "JMP4") (pin "1") (pinfunction "1_1") (pintype "passive"))
      (node (ref "R98") (pin "2") (pinfunction "2_2") (pintype "passive"))
    )
    (net (code "21") (name "/FPGA_SPI_DAC_SS") (class "Default")
      (node (ref "IC11") (pin "1") (pinfunction "~{SYNC}_1") (pintype "input"))
      (node (ref "IC16") (pin "5") (pinfunction "~{SYN}C_5") (pintype "input"))
    )
    (net (code "22") (name "/FPGA_SPI_MOSI") (class "Default")
      (node (ref "IC11") (pin "3") (pinfunction "SDIN_3") (pintype "input"))
      (node (ref "IC16") (pin "7") (pinfunction "DIN_7") (pintype "input"))
    )
    (net (code "23") (name "/FPGA_SPI_SCLK") (class "Default")
      (node (ref "IC11") (pin "2") (pinfunction "SCLK_2") (pintype "input"))
      (node (ref "IC16") (pin "6") (pinfunction "SCLK_6") (pintype "input"))
    )
    (net (code "24") (name "/LM75_OS") (class "Default")
      (node (ref "IC10") (pin "3") (pinfunction "OS_3") (pintype "passive"))
      (node (ref "R62") (pin "1") (pinfunction "1_1") (pintype "passive"))
    )
    (net (code "25") (name "/LMK_CLK") (class "Default")
      (node (ref "IC9") (pin "13") (pinfunction "CLKout2_13") (pintype "passive"))
    )
    (net (code "26") (name "/PG_VCC1P1") (class "Default")
      (node (ref "IC13") (pin "3") (pinfunction "PG_3") (pintype "output"))
      (node (ref "R89") (pin "1") (pinfunction "1_1") (pintype "passive"))
    )
    (net (code "27") (name "/REF_CLK_IN") (class "Default")
      (node (ref "J8") (pin "1") (pinfunction "X_1") (pintype "passive"))
      (node (ref "R66") (pin "1") (pinfunction "1_1") (pintype "passive"))
    )
    (net (code "28") (name "/REF_CLK_OUT") (class "Default")
      (node (ref "IC9") (pin "17") (pinfunction "CLKout4_17") (pintype "passive"))
      (node (ref "J7") (pin "1") (pinfunction "X_1") (pintype "passive"))
    )
    (net (code "29") (name "/RxPLL_CLK") (class "Default")
      (node (ref "C160") (pin "2") (pinfunction "2_2") (pintype "passive"))
      (node (ref "R69") (pin "1") (pinfunction "1_1") (pintype "passive"))
    )
    (net (code "30") (name "/TCXO_DAC_VREF") (class "Default")
      (node (ref "C182") (pin "1") (pinfunction "1_1") (pintype "passive"))
      (node (ref "IC16") (pin "2") (pinfunction "Vref_2") (pintype "input"))
      (node (ref "R73") (pin "1") (pinfunction "1_1") (pintype "passive"))
      (node (ref "R76") (pin "2") (pinfunction "2_2") (pintype "passive"))
      (node (ref "R78") (pin "1") (pinfunction "1_1") (pintype "passive"))
      (node (ref "R81") (pin "1") (pinfunction "1_1") (pintype "passive"))
    )
    (net (code "31") (name "/TxPLL_CLK") (class "Default")
      (node (ref "C158") (pin "2") (pinfunction "2_2") (pintype "passive"))
      (node (ref "R65") (pin "1") (pinfunction "1_1") (pintype "passive"))
    )
    (net (code "32") (name "/XO_VC") (class "Default")
      (node (ref "C163") (pin "2") (pinfunction "2_2") (pintype "passive"))
      (node (ref "C183") (pin "1") (pinfunction "1_1") (pintype "passive"))
      (node (ref "IC16") (pin "3") (pinfunction "Vfb_3") (pintype "input"))
      (node (ref "IC16") (pin "4") (pinfunction "Vout_4") (pintype "output"))
      (node (ref "R71") (pin "1") (pinfunction "1_1") (pintype "passive"))
      (node (ref "R72") (pin "1") (pinfunction "1_1") (pintype "passive"))
      (node (ref "XO1") (pin "1") (pinfunction "VCO_1") (pintype "input"))
    )
    (net (code "33") (name "GND") (class "Default")
      (node (ref "C156") (pin "2") (pinfunction "2_2") (pintype "passive"))
      (node (ref "C157") (pin "1") (pinfunction "1_1") (pintype "passive"))
      (node (ref "C158") (pin "1") (pinfunction "1_1") (pintype "passive"))
      (node (ref "C159") (pin "1") (pinfunction "1_1") (pintype "passive"))
      (node (ref "C160") (pin "1") (pinfunction "1_1") (pintype "passive"))
      (node (ref "C161") (pin "1") (pinfunction "1_1") (pintype "passive"))
      (node (ref "C162") (pin "1") (pinfunction "1_1") (pintype "passive"))
      (node (ref "C163") (pin "1") (pinfunction "1_1") (pintype "passive"))
      (node (ref "C164") (pin "1") (pinfunction "1_1") (pintype "passive"))
      (node (ref "C165") (pin "1") (pinfunction "1_1") (pintype "passive"))
      (node (ref "C166") (pin "1") (pinfunction "1_1") (pintype "passive"))
      (node (ref "C167") (pin "1") (pinfunction "1_1") (pintype "passive"))
      (node (ref "C168") (pin "1") (pinfunction "1_1") (pintype "passive"))
      (node (ref "C169") (pin "1") (pinfunction "1_1") (pintype "passive"))
      (node (ref "C170") (pin "1") (pinfunction "1_1") (pintype "passive"))
      (node (ref "C171") (pin "1") (pinfunction "1_1") (pintype "passive"))
      (node (ref "C172") (pin "1") (pinfunction "1_1") (pintype "passive"))
      (node (ref "C173") (pin "1") (pinfunction "1_1") (pintype "passive"))
      (node (ref "C174") (pin "2") (pinfunction "2_2") (pintype "passive"))
      (node (ref "C175") (pin "2") (pinfunction "2_2") (pintype "passive"))
      (node (ref "C176") (pin "2") (pinfunction "2_2") (pintype "passive"))
      (node (ref "C177") (pin "1") (pinfunction "1_1") (pintype "passive"))
      (node (ref "C178") (pin "1") (pinfunction "1_1") (pintype "passive"))
      (node (ref "C179") (pin "1") (pinfunction "1_1") (pintype "passive"))
      (node (ref "C180") (pin "1") (pinfunction "1_1") (pintype "passive"))
      (node (ref "C181") (pin "2") (pinfunction "2_2") (pintype "passive"))
      (node (ref "C182") (pin "2") (pinfunction "2_2") (pintype "passive"))
      (node (ref "C183") (pin "2") (pinfunction "2_2") (pintype "passive"))
      (node (ref "C184") (pin "2") (pinfunction "2_2") (pintype "passive"))
      (node (ref "C185") (pin "2") (pinfunction "2_2") (pintype "passive"))
      (node (ref "C186") (pin "1") (pinfunction "1_1") (pintype "passive"))
      (node (ref "C187") (pin "1") (pinfunction "1_1") (pintype "passive"))
      (node (ref "C188") (pin "1") (pinfunction "1_1") (pintype "passive"))
      (node (ref "C189") (pin "1") (pinfunction "1_1") (pintype "passive"))
      (node (ref "C190") (pin "1") (pinfunction "1_1") (pintype "passive"))
      (node (ref "C191") (pin "1") (pinfunction "1_1") (pintype "passive"))
      (node (ref "C192") (pin "1") (pinfunction "1_1") (pintype "passive"))
      (node (ref "C193") (pin "2") (pinfunction "2_2") (pintype "passive"))
      (node (ref "C194") (pin "1") (pinfunction "1_1") (pintype "passive"))
      (node (ref "C195") (pin "2") (pinfunction "2_2") (pintype "passive"))
      (node (ref "C196") (pin "1") (pinfunction "1_1") (pintype "passive"))
      (node (ref "C197") (pin "1") (pinfunction "1_1") (pintype "passive"))
      (node (ref "C198") (pin "1") (pinfunction "1_1") (pintype "passive"))
      (node (ref "IC10") (pin "4") (pinfunction "GND_4") (pintype "passive"))
      (node (ref "IC10") (pin "5") (pinfunction "A2_5") (pintype "passive"))
      (node (ref "IC10") (pin "6") (pinfunction "A1_6") (pintype "passive"))
      (node (ref "IC10") (pin "7") (pinfunction "A0_7") (pintype "passive"))
      (node (ref "IC11") (pin "5") (pinfunction "GND_5") (pintype "power_in"))
      (node (ref "IC12") (pin "1") (pinfunction "E0_1") (pintype "input"))
      (node (ref "IC12") (pin "2") (pinfunction "E1_2") (pintype "input"))
      (node (ref "IC12") (pin "3") (pinfunction "E2_3") (pintype "input"))
      (node (ref "IC12") (pin "4") (pinfunction "VSS_4") (pintype "power_in"))
      (node (ref "IC12") (pin "7") (pinfunction "~{WC}_7") (pintype "input"))
      (node (ref "IC12") (pin "PAD") (pinfunction "PAD_PAD") (pintype "power_in"))
      (node (ref "IC13") (pin "2") (pinfunction "GND_2") (pintype "passive"))
      (node (ref "IC13") (pin "PAD") (pinfunction "PAD_PAD") (pintype "passive"))
      (node (ref "IC14") (pin "4") (pinfunction "SGND_4") (pintype "passive"))
      (node (ref "IC14") (pin "6") (pinfunction "PGND_6") (pintype "passive"))
      (node (ref "IC14") (pin "PAD") (pinfunction "PAD_(SGND)_PAD") (pintype "passive"))
      (node (ref "IC15") (pin "3") (pinfunction "W_3") (pintype "passive"))
      (node (ref "IC15") (pin "4") (pinfunction "GND_4") (pintype "passive"))
      (node (ref "IC15") (pin "PAD") (pinfunction "GND_PAD") (pintype "passive"))
      (node (ref "IC16") (pin "8") (pinfunction "GND_8") (pintype "passive"))
      (node (ref "IC17") (pin "3") (pinfunction "VSS_3") (pintype "power_in"))
      (node (ref "IC18") (pin "2") (pinfunction "GND_2") (pintype "passive"))
      (node (ref "IC18") (pin "PAD") (pinfunction "PAD_PAD") (pintype "passive"))
      (node (ref "IC19") (pin "4") (pinfunction "SGND_4") (pintype "passive"))
      (node (ref "IC19") (pin "6") (pinfunction "PGND_6") (pintype "passive"))
      (node (ref "IC19") (pin "PAD") (pinfunction "PAD_(SGND)_PAD") (pintype "passive"))
      (node (ref "IC9") (pin "1") (pinfunction "GND_1") (pintype "passive"))
      (node (ref "IC9") (pin "11") (pinfunction "GND_11") (pintype "passive"))
      (node (ref "IC9") (pin "12") (pinfunction "GND_12") (pintype "passive"))
      (node (ref "IC9") (pin "16") (pinfunction "GND_16") (pintype "passive"))
      (node (ref "IC9") (pin "19") (pinfunction "GND_19") (pintype "passive"))
      (node (ref "IC9") (pin "22") (pinfunction "SEL_22") (pintype "passive"))
      (node (ref "IC9") (pin "25") (pinfunction "GND_25") (pintype "passive"))
      (node (ref "IC9") (pin "7") (pinfunction "GND_7") (pintype "passive"))
      (node (ref "J7") (pin "2") (pinfunction "Y_2") (pintype "passive"))
      (node (ref "J8") (pin "2") (pinfunction "Y_2") (pintype "passive"))
      (node (ref "R67") (pin "1") (pinfunction "1_1") (pintype "passive"))
      (node (ref "R72") (pin "2") (pinfunction "2_2") (pintype "passive"))
      (node (ref "R80") (pin "2") (pinfunction "2_2") (pintype "passive"))
      (node (ref "R81") (pin "2") (pinfunction "2_2") (pintype "passive"))
      (node (ref "R82") (pin "1") (pinfunction "1_1") (pintype "passive"))
      (node (ref "R88") (pin "2") (pinfunction "2_2") (pintype "passive"))
      (node (ref "R90") (pin "1") (pinfunction "1_1") (pintype "passive"))
      (node (ref "R99") (pin "1") (pinfunction "1_1") (pintype "passive"))
      (node (ref "VT4") (pin "S") (pinfunction "S_S") (pintype "passive"))
      (node (ref "XO1") (pin "4") (pinfunction "GND_4") (pintype "passive"))
    )
    (net (code "34") (name "Net-(C154-Pad1)") (class "Default")
      (node (ref "C154") (pin "1") (pinfunction "1_1") (pintype "passive"))
      (node (ref "C155") (pin "2") (pinfunction "2_2") (pintype "passive"))
      (node (ref "R67") (pin "2") (pinfunction "2_2") (pintype "passive"))
    )
    (net (code "35") (name "Net-(C154-Pad2)") (class "Default")
      (node (ref "C154") (pin "2") (pinfunction "2_2") (pintype "passive"))
      (node (ref "R63") (pin "2") (pinfunction "2_2") (pintype "passive"))
      (node (ref "R66") (pin "2") (pinfunction "2_2") (pintype "passive"))
    )
    (net (code "36") (name "Net-(C159-Pad2)") (class "Default")
      (node (ref "C159") (pin "2") (pinfunction "2_2") (pintype "passive"))
      (node (ref "FR38") (pin "1") (pinfunction "1_1") (pintype "passive"))
      (node (ref "R64") (pin "1") (pinfunction "1_1") (pintype "passive"))
    )
    (net (code "37") (name "Net-(C195-Pad1)") (class "Default")
      (node (ref "C195") (pin "1") (pinfunction "1_1") (pintype "passive"))
      (node (ref "J9") (pin "2") (pinfunction "2_2") (pintype "passive"))
      (node (ref "R93") (pin "2") (pinfunction "2_2") (pintype "passive"))
      (node (ref "R95") (pin "2") (pinfunction "2_2") (pintype "passive"))
    )
    (net (code "38") (name "Net-(IC9-CLKin)") (class "Default")
      (node (ref "C155") (pin "1") (pinfunction "1_1") (pintype "passive"))
      (node (ref "IC9") (pin "21") (pinfunction "CLKin_21") (pintype "passive"))
    )
    (net (code "39") (name "Net-(IC9-CLKin*)") (class "Default")
      (node (ref "C162") (pin "2") (pinfunction "2_2") (pintype "passive"))
      (node (ref "IC9") (pin "20") (pinfunction "CLKin*_20") (pintype "passive"))
    )
    (net (code "40") (name "Net-(IC9-CLKout0)") (class "Default")
      (node (ref "IC9") (pin "3") (pinfunction "CLKout0_3") (pintype "passive"))
      (node (ref "R65") (pin "2") (pinfunction "2_2") (pintype "passive"))
    )
    (net (code "41") (name "Net-(IC9-CLKout1)") (class "Default")
      (node (ref "IC9") (pin "5") (pinfunction "CLKout1_5") (pintype "passive"))
      (node (ref "R69") (pin "2") (pinfunction "2_2") (pintype "passive"))
    )
    (net (code "42") (name "Net-(IC9-OE)") (class "Default")
      (node (ref "IC9") (pin "24") (pinfunction "OE_24") (pintype "passive"))
      (node (ref "R61") (pin "1") (pinfunction "1_1") (pintype "passive"))
    )
    (net (code "43") (name "Net-(IC11-VDD)") (class "Default")
      (node (ref "C175") (pin "1") (pinfunction "1_1") (pintype "passive"))
      (node (ref "FR41") (pin "2") (pinfunction "2_2") (pintype "passive"))
      (node (ref "IC11") (pin "4") (pinfunction "VDD_4") (pintype "power_in"))
    )
    (net (code "44") (name "Net-(IC11-VOUT)") (class "Default")
      (node (ref "IC11") (pin "6") (pinfunction "VOUT_6") (pintype "tri_state"))
      (node (ref "R71") (pin "2") (pinfunction "2_2") (pintype "passive"))
    )
    (net (code "45") (name "Net-(IC13-ADJ)") (class "Default")
      (node (ref "IC13") (pin "5") (pinfunction "ADJ_5") (pintype "input"))
      (node (ref "R74") (pin "1") (pinfunction "1_1") (pintype "passive"))
      (node (ref "R80") (pin "1") (pinfunction "1_1") (pintype "passive"))
    )
    (net (code "46") (name "Net-(IC14-VCON)") (class "Default")
      (node (ref "C184") (pin "1") (pinfunction "1_1") (pintype "passive"))
      (node (ref "IC14") (pin "2") (pinfunction "VCON_2") (pintype "input"))
      (node (ref "R79") (pin "1") (pinfunction "1_1") (pintype "passive"))
      (node (ref "R82") (pin "2") (pinfunction "2_2") (pintype "passive"))
    )
    (net (code "47") (name "Net-(IC14-VREF)") (class "Default")
      (node (ref "IC14") (pin "8") (pinfunction "VREF_8") (pintype "output"))
      (node (ref "R79") (pin "2") (pinfunction "2_2") (pintype "passive"))
    )
    (net (code "48") (name "Net-(IC16-Vdd)") (class "Default")
      (node (ref "C176") (pin "1") (pinfunction "1_1") (pintype "passive"))
      (node (ref "FR42") (pin "2") (pinfunction "2_2") (pintype "passive"))
      (node (ref "IC16") (pin "1") (pinfunction "Vdd_1") (pintype "power_in"))
      (node (ref "R73") (pin "2") (pinfunction "2_2") (pintype "passive"))
    )
    (net (code "49") (name "Net-(IC17-IN)") (class "Default")
      (node (ref "C185") (pin "1") (pinfunction "1_1") (pintype "passive"))
      (node (ref "C187") (pin "2") (pinfunction "2_2") (pintype "passive"))
      (node (ref "FR43") (pin "2") (pinfunction "2_2") (pintype "passive"))
      (node (ref "IC17") (pin "1") (pinfunction "IN_1") (pintype "power_in"))
    )
    (net (code "50") (name "Net-(IC18-ADJ)") (class "Default")
      (node (ref "IC18") (pin "5") (pinfunction "ADJ_5") (pintype "input"))
      (node (ref "R83") (pin "1") (pinfunction "1_1") (pintype "passive"))
      (node (ref "R88") (pin "1") (pinfunction "1_1") (pintype "passive"))
    )
    (net (code "51") (name "Net-(IC18-PG)") (class "Default")
      (node (ref "C192") (pin "2") (pinfunction "2_2") (pintype "passive"))
      (node (ref "IC18") (pin "3") (pinfunction "PG_3") (pintype "output"))
    )
    (net (code "52") (name "Net-(IC19-VCON)") (class "Default")
      (node (ref "C193") (pin "1") (pinfunction "1_1") (pintype "passive"))
      (node (ref "IC19") (pin "2") (pinfunction "VCON_2") (pintype "input"))
      (node (ref "R87") (pin "1") (pinfunction "1_1") (pintype "passive"))
      (node (ref "R90") (pin "2") (pinfunction "2_2") (pintype "passive"))
    )
    (net (code "53") (name "Net-(IC19-VREF)") (class "Default")
      (node (ref "IC19") (pin "8") (pinfunction "VREF_8") (pintype "output"))
      (node (ref "R87") (pin "2") (pinfunction "2_2") (pintype "passive"))
    )
    (net (code "54") (name "Net-(J9-Pad1)") (class "Default")
      (node (ref "J9") (pin "1") (pinfunction "1_1") (pintype "passive"))
      (node (ref "R99") (pin "2") (pinfunction "2_2") (pintype "passive"))
      (node (ref "VT4") (pin "D") (pinfunction "D_D") (pintype "passive"))
    )
    (net (code "55") (name "Net-(LED1-Pad3)") (class "Default")
      (node (ref "LED1") (pin "3") (pinfunction "3_3") (pintype "power_in"))
      (node (ref "R84") (pin "1") (pinfunction "1_1") (pintype "passive"))
    )
    (net (code "56") (name "Net-(LED1-Pad4)") (class "Default")
      (node (ref "LED1") (pin "4") (pinfunction "4_4") (pintype "power_in"))
      (node (ref "R86") (pin "1") (pinfunction "1_1") (pintype "passive"))
    )
    (net (code "57") (name "Net-(LED2-Pad3)") (class "Default")
      (node (ref "LED2") (pin "3") (pinfunction "3_3") (pintype "power_in"))
      (node (ref "R91") (pin "1") (pinfunction "1_1") (pintype "passive"))
    )
    (net (code "58") (name "Net-(LED2-Pad4)") (class "Default")
      (node (ref "LED2") (pin "4") (pinfunction "4_4") (pintype "power_in"))
      (node (ref "R94") (pin "1") (pinfunction "1_1") (pintype "passive"))
    )
    (net (code "59") (name "Net-(LED3-Pad3)") (class "Default")
      (node (ref "LED3") (pin "3") (pinfunction "3_3") (pintype "power_in"))
      (node (ref "R96") (pin "1") (pinfunction "1_1") (pintype "passive"))
    )
    (net (code "60") (name "Net-(LED3-Pad4)") (class "Default")
      (node (ref "LED3") (pin "4") (pinfunction "4_4") (pintype "power_in"))
      (node (ref "R98") (pin "1") (pinfunction "1_1") (pintype "passive"))
    )
    (net (code "61") (name "Net-(XO1-RF_OUT)") (class "Default")
      (node (ref "R63") (pin "1") (pinfunction "1_1") (pintype "passive"))
      (node (ref "XO1") (pin "6") (pinfunction "RF_OUT_6") (pintype "output"))
    )
    (net (code "62") (name "Net-(XO1-VCC)") (class "Default")
      (node (ref "C161") (pin "2") (pinfunction "2_2") (pintype "passive"))
      (node (ref "FR38") (pin "2") (pinfunction "2_2") (pintype "passive"))
      (node (ref "XO1") (pin "9") (pinfunction "VCC_9") (pintype "power_in"))
    )
    (net (code "63") (name "Net-(XO1-VC_FILTER)") (class "Default")
      (node (ref "C157") (pin "2") (pinfunction "2_2") (pintype "passive"))
      (node (ref "XO1") (pin "7") (pinfunction "VC_FILTER_7") (pintype "input"))
    )
    (net (code "64") (name "VCC1P1") (class "Default")
      (node (ref "C180") (pin "2") (pinfunction "2_2") (pintype "passive"))
      (node (ref "IC13") (pin "4") (pinfunction "Vout_4") (pintype "output"))
      (node (ref "R74") (pin "2") (pinfunction "2_2") (pintype "passive"))
    )
    (net (code "65") (name "VCC1P8") (class "Default")
      (node (ref "C178") (pin "2") (pinfunction "2_2") (pintype "passive"))
      (node (ref "C179") (pin "2") (pinfunction "2_2") (pintype "passive"))
      (node (ref "FR40") (pin "1") (pinfunction "1_1") (pintype "passive"))
      (node (ref "IC13") (pin "1") (pinfunction "EN_1") (pintype "input"))
      (node (ref "IC13") (pin "6") (pinfunction "Vin_6") (pintype "input"))
      (node (ref "IC14") (pin "3") (pinfunction "FB_3") (pintype "input"))
      (node (ref "IC14") (pin "5") (pinfunction "VOUT_5") (pintype "output"))
      (node (ref "R62") (pin "2") (pinfunction "2_2") (pintype "passive"))
      (node (ref "R92") (pin "2") (pinfunction "2_2") (pintype "passive"))
    )
    (net (code "66") (name "VCC2P5") (class "Default")
      (node (ref "C191") (pin "2") (pinfunction "2_2") (pintype "passive"))
      (node (ref "IC18") (pin "4") (pinfunction "Vout_4") (pintype "output"))
      (node (ref "R78") (pin "2") (pinfunction "2_2") (pintype "passive"))
      (node (ref "R83") (pin "2") (pinfunction "2_2") (pintype "passive"))
      (node (ref "R97") (pin "1") (pinfunction "1_1") (pintype "passive"))
    )
    (net (code "67") (name "VCC2P5_VREF") (class "Default")
      (node (ref "C186") (pin "2") (pinfunction "2_2") (pintype "passive"))
      (node (ref "IC17") (pin "2") (pinfunction "OUT_2") (pintype "power_in"))
      (node (ref "R76") (pin "1") (pinfunction "1_1") (pintype "passive"))
    )
    (net (code "68") (name "VCC3P3") (class "Default")
      (node (ref "C156") (pin "1") (pinfunction "1_1") (pintype "passive"))
      (node (ref "C174") (pin "1") (pinfunction "1_1") (pintype "passive"))
      (node (ref "C181") (pin "1") (pinfunction "1_1") (pintype "passive"))
      (node (ref "C189") (pin "2") (pinfunction "2_2") (pintype "passive"))
      (node (ref "C190") (pin "2") (pinfunction "2_2") (pintype "passive"))
      (node (ref "FR44") (pin "1") (pinfunction "1_1") (pintype "passive"))
      (node (ref "IC10") (pin "8") (pinfunction "VCC_8") (pintype "passive"))
      (node (ref "IC12") (pin "8") (pinfunction "VCC_8") (pintype "power_in"))
      (node (ref "IC15") (pin "7") (pinfunction "HOLD_7") (pintype "passive"))
      (node (ref "IC15") (pin "8") (pinfunction "VCC_8") (pintype "passive"))
      (node (ref "IC18") (pin "1") (pinfunction "EN_1") (pintype "input"))
      (node (ref "IC18") (pin "6") (pinfunction "Vin_6") (pintype "input"))
      (node (ref "IC19") (pin "3") (pinfunction "FB_3") (pintype "input"))
      (node (ref "IC19") (pin "5") (pinfunction "VOUT_5") (pintype "output"))
      (node (ref "LED1") (pin "1") (pinfunction "1_1") (pintype "power_in"))
      (node (ref "LED1") (pin "2") (pinfunction "2_2") (pintype "power_in"))
      (node (ref "LED2") (pin "1") (pinfunction "1_1") (pintype "power_in"))
      (node (ref "LED2") (pin "2") (pinfunction "2_2") (pintype "power_in"))
      (node (ref "LED3") (pin "1") (pinfunction "1_1") (pintype "power_in"))
      (node (ref "LED3") (pin "2") (pinfunction "2_2") (pintype "power_in"))
      (node (ref "R100") (pin "1") (pinfunction "1_1") (pintype "passive"))
      (node (ref "R68") (pin "1") (pinfunction "1_1") (pintype "passive"))
      (node (ref "R70") (pin "1") (pinfunction "1_1") (pintype "passive"))
      (node (ref "R75") (pin "2") (pinfunction "2_2") (pintype "passive"))
      (node (ref "R77") (pin "2") (pinfunction "2_2") (pintype "passive"))
      (node (ref "R95") (pin "1") (pinfunction "1_1") (pintype "passive"))
    )
    (net (code "69") (name "VCC3P3_CLK") (class "Default")
      (node (ref "C196") (pin "2") (pinfunction "2_2") (pintype "passive"))
      (node (ref "FR39") (pin "1") (pinfunction "1_1") (pintype "passive"))
      (node (ref "FR41") (pin "1") (pinfunction "1_1") (pintype "passive"))
      (node (ref "FR42") (pin "1") (pinfunction "1_1") (pintype "passive"))
      (node (ref "FR43") (pin "1") (pinfunction "1_1") (pintype "passive"))
      (node (ref "FR44") (pin "2") (pinfunction "2_2") (pintype "passive"))
      (node (ref "R64") (pin "2") (pinfunction "2_2") (pintype "passive"))
    )
    (net (code "70") (name "VCC5P0") (class "Default")
      (node (ref "C177") (pin "2") (pinfunction "2_2") (pintype "passive"))
      (node (ref "C188") (pin "2") (pinfunction "2_2") (pintype "passive"))
      (node (ref "IC14") (pin "1") (pinfunction "EN_1") (pintype "input"))
      (node (ref "IC14") (pin "7") (pinfunction "VIN_7") (pintype "input"))
      (node (ref "IC19") (pin "7") (pinfunction "VIN_7") (pintype "input"))
      (node (ref "R85") (pin "2") (pinfunction "2_2") (pintype "passive"))
      (node (ref "R93") (pin "1") (pinfunction "1_1") (pintype "passive"))
    )
    (net (code "71") (name "VDIO_LMS") (class "Default")
      (node (ref "C198") (pin "2") (pinfunction "2_2") (pintype "passive"))
      (node (ref "FR45") (pin "2") (pinfunction "2_2") (pintype "passive"))
    )
    (net (code "72") (name "VDIO_LMS_FPGA") (class "Default")
      (node (ref "C197") (pin "2") (pinfunction "2_2") (pintype "passive"))
      (node (ref "FR45") (pin "1") (pinfunction "1_1") (pintype "passive"))
      (node (ref "R100") (pin "2") (pinfunction "2_2") (pintype "passive"))
      (node (ref "R97") (pin "2") (pinfunction "2_2") (pintype "passive"))
    )
    (net (code "73") (name "unconnected-(IC9-CLKout3-Pad15)") (class "Default")
      (node (ref "IC9") (pin "15") (pinfunction "CLKout3_15") (pintype "passive+no_connect"))
    )
    (net (code "74") (name "unconnected-(IC9-OSCin-Pad9)") (class "Default")
      (node (ref "IC9") (pin "9") (pinfunction "OSCin_9") (pintype "passive+no_connect"))
    )
    (net (code "75") (name "unconnected-(IC9-OSCout-Pad10)") (class "Default")
      (node (ref "IC9") (pin "10") (pinfunction "OSCout_10") (pintype "passive+no_connect"))
    )
    (net (code "76") (name "unconnected-(XO1-NC-Pad2)") (class "Default")
      (node (ref "XO1") (pin "2") (pinfunction "NC_2") (pintype "passive+no_connect"))
    )
    (net (code "77") (name "unconnected-(XO1-NC-Pad3)") (class "Default")
      (node (ref "XO1") (pin "3") (pinfunction "NC_3") (pintype "passive+no_connect"))
    )
    (net (code "78") (name "unconnected-(XO1-NC-Pad5)") (class "Default")
      (node (ref "XO1") (pin "5") (pinfunction "NC_5") (pintype "passive+no_connect"))
    )
    (net (code "79") (name "unconnected-(XO1-NC-Pad8)") (class "Default")
      (node (ref "XO1") (pin "8") (pinfunction "NC_8") (pintype "passive+no_connect"))
    )
    (net (code "80") (name "unconnected-(XO1-NC-Pad10)") (class "Default")
      (node (ref "XO1") (pin "10") (pinfunction "NC_10") (pintype "passive+no_connect"))
    )
  )
)
